# small_line.net
KiCad netlist of a schematic drawn in EAGLE
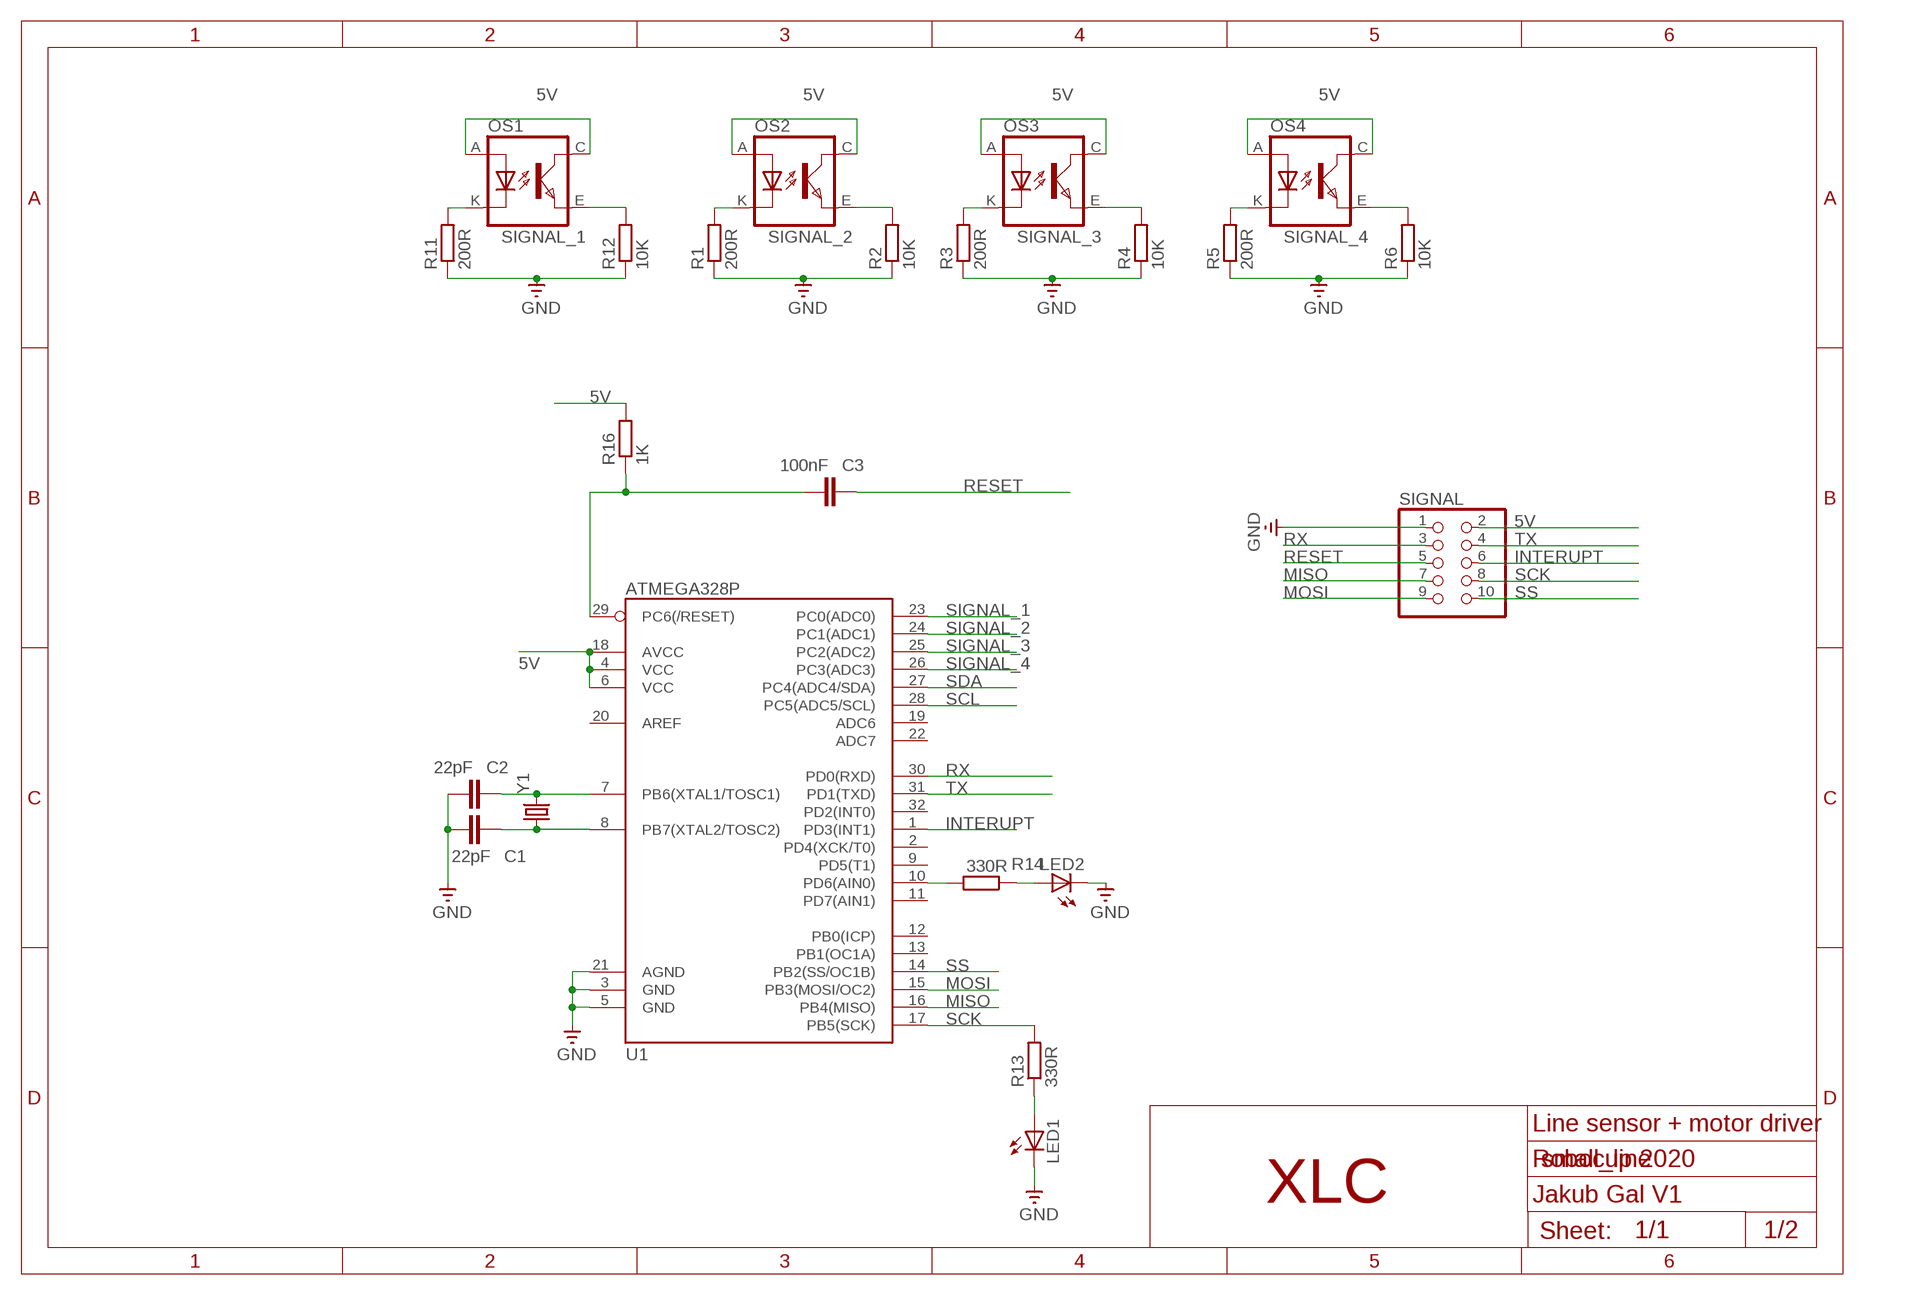
[diagram p0: schematic, sheet 1]

(export (version "E")
  (design (tool "Eeschema 10.0.6"))
  (components
    (comp (ref "C1")
      (value "22pF")
      (footprint "eagle-import:C0603")
      (libsource (lib "eagle-import") (part "C-EUC0603"))
    )
    (comp (ref "C2")
      (value "22pF")
      (footprint "eagle-import:C0603")
      (libsource (lib "eagle-import") (part "C-EUC0603"))
    )
    (comp (ref "C3")
      (value "100nF")
      (footprint "eagle-import:C0603")
      (libsource (lib "eagle-import") (part "C-EUC0603"))
    )
    (comp (ref "LED1")
      (value "LEDCHIPLED_0603")
      (footprint "eagle-import:CHIPLED_0603")
      (libsource (lib "eagle-import") (part "LEDCHIPLED_0603"))
    )
    (comp (ref "LED2")
      (value "LEDCHIPLED_0603")
      (footprint "eagle-import:CHIPLED_0603")
      (libsource (lib "eagle-import") (part "LEDCHIPLED_0603"))
    )
    (comp (ref "OS1")
      (value "TCRT5000")
      (footprint "eagle-import:TCRT5000")
      (libsource (lib "eagle-import") (part "TCRT5000"))
    )
    (comp (ref "OS2")
      (value "TCRT5000")
      (footprint "eagle-import:TCRT5000")
      (libsource (lib "eagle-import") (part "TCRT5000"))
    )
    (comp (ref "OS3")
      (value "TCRT5000")
      (footprint "eagle-import:TCRT5000")
      (libsource (lib "eagle-import") (part "TCRT5000"))
    )
    (comp (ref "OS4")
      (value "TCRT5000")
      (footprint "eagle-import:TCRT5000")
      (libsource (lib "eagle-import") (part "TCRT5000"))
    )
    (comp (ref "R1")
      (value "200R")
      (footprint "eagle-import:R0603")
      (libsource (lib "eagle-import") (part "R-EU_R0603"))
    )
    (comp (ref "R2")
      (value "10K")
      (footprint "eagle-import:R0603")
      (libsource (lib "eagle-import") (part "R-EU_R0603"))
    )
    (comp (ref "R3")
      (value "200R")
      (footprint "eagle-import:R0603")
      (libsource (lib "eagle-import") (part "R-EU_R0603"))
    )
    (comp (ref "R4")
      (value "10K")
      (footprint "eagle-import:R0603")
      (libsource (lib "eagle-import") (part "R-EU_R0603"))
    )
    (comp (ref "R5")
      (value "200R")
      (footprint "eagle-import:R0603")
      (libsource (lib "eagle-import") (part "R-EU_R0603"))
    )
    (comp (ref "R6")
      (value "10K")
      (footprint "eagle-import:R0603")
      (libsource (lib "eagle-import") (part "R-EU_R0603"))
    )
    (comp (ref "R11")
      (value "200R")
      (footprint "eagle-import:R0603")
      (libsource (lib "eagle-import") (part "R-EU_R0603"))
    )
    (comp (ref "R12")
      (value "10K")
      (footprint "eagle-import:R0603")
      (libsource (lib "eagle-import") (part "R-EU_R0603"))
    )
    (comp (ref "R13")
      (value "330R")
      (footprint "eagle-import:R0603")
      (libsource (lib "eagle-import") (part "R-EU_R0603"))
    )
    (comp (ref "R14")
      (value "330R")
      (footprint "eagle-import:R0603")
      (libsource (lib "eagle-import") (part "R-EU_R0603"))
    )
    (comp (ref "R16")
      (value "1K")
      (footprint "eagle-import:R0603")
      (libsource (lib "eagle-import") (part "R-EU_R0603"))
    )
    (comp (ref "SIGNAL")
      (value "PINHD-2X5")
      (footprint "eagle-import:2X05")
      (libsource (lib "eagle-import") (part "PINHD-2X5"))
    )
    (comp (ref "U1")
      (value "ATMEGA328P")
      (footprint "eagle-import:TQFP32-08")
      (libsource (lib "eagle-import") (part "ATMEGA328_SMT"))
    )
    (comp (ref "Y1")
      (value "CRYSTALHC49US")
      (footprint "eagle-import:HC49US")
      (libsource (lib "eagle-import") (part "CRYSTALHC49US"))
    )
  )
  (nets
    (net (code "1") (name "/5V") (class "Default")
      (node (ref "OS1") (pin "A") (pinfunction "ANODE_A") (pintype "passive"))
      (node (ref "OS1") (pin "C") (pinfunction "COLLECTOR_C") (pintype "passive"))
      (node (ref "OS2") (pin "A") (pinfunction "ANODE_A") (pintype "passive"))
      (node (ref "OS2") (pin "C") (pinfunction "COLLECTOR_C") (pintype "passive"))
      (node (ref "OS3") (pin "A") (pinfunction "ANODE_A") (pintype "passive"))
      (node (ref "OS3") (pin "C") (pinfunction "COLLECTOR_C") (pintype "passive"))
      (node (ref "OS4") (pin "A") (pinfunction "ANODE_A") (pintype "passive"))
      (node (ref "OS4") (pin "C") (pinfunction "COLLECTOR_C") (pintype "passive"))
      (node (ref "R16") (pin "2") (pinfunction "2_2") (pintype "passive"))
      (node (ref "SIGNAL") (pin "2") (pinfunction "2_2") (pintype "passive"))
      (node (ref "U1") (pin "18") (pinfunction "AVCC_18") (pintype "bidirectional"))
      (node (ref "U1") (pin "4") (pinfunction "VCC_4") (pintype "bidirectional"))
      (node (ref "U1") (pin "6") (pinfunction "VCC_6") (pintype "bidirectional"))
    )
    (net (code "2") (name "/INTERUPT") (class "Default")
      (node (ref "SIGNAL") (pin "6") (pinfunction "6_6") (pintype "passive"))
      (node (ref "U1") (pin "1") (pinfunction "PD3(INT1)_1") (pintype "bidirectional"))
    )
    (net (code "3") (name "/MISO") (class "Default")
      (node (ref "SIGNAL") (pin "7") (pinfunction "7_7") (pintype "passive"))
      (node (ref "U1") (pin "16") (pinfunction "PB4(MISO)_16") (pintype "bidirectional"))
    )
    (net (code "4") (name "/MOSI") (class "Default")
      (node (ref "SIGNAL") (pin "9") (pinfunction "9_9") (pintype "passive"))
      (node (ref "U1") (pin "15") (pinfunction "PB3(MOSI/OC2)_15") (pintype "bidirectional"))
    )
    (net (code "5") (name "/RESET") (class "Default")
      (node (ref "C3") (pin "2") (pinfunction "2_2") (pintype "passive"))
      (node (ref "SIGNAL") (pin "5") (pinfunction "5_5") (pintype "passive"))
    )
    (net (code "6") (name "/RX") (class "Default")
      (node (ref "SIGNAL") (pin "3") (pinfunction "3_3") (pintype "passive"))
      (node (ref "U1") (pin "30") (pinfunction "PD0(RXD)_30") (pintype "bidirectional"))
    )
    (net (code "7") (name "/SCK") (class "Default")
      (node (ref "R13") (pin "2") (pinfunction "2_2") (pintype "passive"))
      (node (ref "SIGNAL") (pin "8") (pinfunction "8_8") (pintype "passive"))
      (node (ref "U1") (pin "17") (pinfunction "PB5(SCK)_17") (pintype "bidirectional"))
    )
    (net (code "8") (name "/SCL") (class "Default")
      (node (ref "U1") (pin "28") (pinfunction "PC5(ADC5/SCL)_28") (pintype "bidirectional"))
    )
    (net (code "9") (name "/SDA") (class "Default")
      (node (ref "U1") (pin "27") (pinfunction "PC4(ADC4/SDA)_27") (pintype "bidirectional"))
    )
    (net (code "10") (name "/SIGNAL_1") (class "Default")
      (node (ref "OS1") (pin "E") (pinfunction "EMITTER_E") (pintype "passive"))
      (node (ref "R12") (pin "2") (pinfunction "2_2") (pintype "passive"))
      (node (ref "U1") (pin "23") (pinfunction "PC0(ADC0)_23") (pintype "bidirectional"))
    )
    (net (code "11") (name "/SIGNAL_2") (class "Default")
      (node (ref "OS2") (pin "E") (pinfunction "EMITTER_E") (pintype "passive"))
      (node (ref "R2") (pin "2") (pinfunction "2_2") (pintype "passive"))
      (node (ref "U1") (pin "24") (pinfunction "PC1(ADC1)_24") (pintype "bidirectional"))
    )
    (net (code "12") (name "/SIGNAL_3") (class "Default")
      (node (ref "OS3") (pin "E") (pinfunction "EMITTER_E") (pintype "passive"))
      (node (ref "R4") (pin "2") (pinfunction "2_2") (pintype "passive"))
      (node (ref "U1") (pin "25") (pinfunction "PC2(ADC2)_25") (pintype "bidirectional"))
    )
    (net (code "13") (name "/SIGNAL_4") (class "Default")
      (node (ref "OS4") (pin "E") (pinfunction "EMITTER_E") (pintype "passive"))
      (node (ref "R6") (pin "2") (pinfunction "2_2") (pintype "passive"))
      (node (ref "U1") (pin "26") (pinfunction "PC3(ADC3)_26") (pintype "bidirectional"))
    )
    (net (code "14") (name "/SS") (class "Default")
      (node (ref "SIGNAL") (pin "10") (pinfunction "10_10") (pintype "passive"))
      (node (ref "U1") (pin "14") (pinfunction "PB2(SS/OC1B)_14") (pintype "bidirectional"))
    )
    (net (code "15") (name "/TX") (class "Default")
      (node (ref "SIGNAL") (pin "4") (pinfunction "4_4") (pintype "passive"))
      (node (ref "U1") (pin "31") (pinfunction "PD1(TXD)_31") (pintype "bidirectional"))
    )
    (net (code "16") (name "GND") (class "Default")
      (node (ref "C1") (pin "1") (pinfunction "1_1") (pintype "passive"))
      (node (ref "C2") (pin "1") (pinfunction "1_1") (pintype "passive"))
      (node (ref "LED1") (pin "C") (pinfunction "C_C") (pintype "passive"))
      (node (ref "LED2") (pin "C") (pinfunction "C_C") (pintype "passive"))
      (node (ref "R1") (pin "1") (pinfunction "1_1") (pintype "passive"))
      (node (ref "R11") (pin "1") (pinfunction "1_1") (pintype "passive"))
      (node (ref "R12") (pin "1") (pinfunction "1_1") (pintype "passive"))
      (node (ref "R2") (pin "1") (pinfunction "1_1") (pintype "passive"))
      (node (ref "R3") (pin "1") (pinfunction "1_1") (pintype "passive"))
      (node (ref "R4") (pin "1") (pinfunction "1_1") (pintype "passive"))
      (node (ref "R5") (pin "1") (pinfunction "1_1") (pintype "passive"))
      (node (ref "R6") (pin "1") (pinfunction "1_1") (pintype "passive"))
      (node (ref "SIGNAL") (pin "1") (pinfunction "1_1") (pintype "passive"))
      (node (ref "U1") (pin "21") (pinfunction "AGND_21") (pintype "bidirectional"))
      (node (ref "U1") (pin "3") (pinfunction "GND_3") (pintype "bidirectional"))
      (node (ref "U1") (pin "5") (pinfunction "GND_5") (pintype "bidirectional"))
    )
    (net (code "17") (name "Net-(LED1-PadA)") (class "Default")
      (node (ref "LED1") (pin "A") (pinfunction "A_A") (pintype "passive"))
      (node (ref "R13") (pin "1") (pinfunction "1_1") (pintype "passive"))
    )
    (net (code "18") (name "Net-(LED2-PadA)") (class "Default")
      (node (ref "LED2") (pin "A") (pinfunction "A_A") (pintype "passive"))
      (node (ref "R14") (pin "1") (pinfunction "1_1") (pintype "passive"))
    )
    (net (code "19") (name "Net-(OS1-CATHODE)") (class "Default")
      (node (ref "OS1") (pin "K") (pinfunction "CATHODE_K") (pintype "passive"))
      (node (ref "R11") (pin "2") (pinfunction "2_2") (pintype "passive"))
    )
    (net (code "20") (name "Net-(OS2-CATHODE)") (class "Default")
      (node (ref "OS2") (pin "K") (pinfunction "CATHODE_K") (pintype "passive"))
      (node (ref "R1") (pin "2") (pinfunction "2_2") (pintype "passive"))
    )
    (net (code "21") (name "Net-(OS3-CATHODE)") (class "Default")
      (node (ref "OS3") (pin "K") (pinfunction "CATHODE_K") (pintype "passive"))
      (node (ref "R3") (pin "2") (pinfunction "2_2") (pintype "passive"))
    )
    (net (code "22") (name "Net-(OS4-CATHODE)") (class "Default")
      (node (ref "OS4") (pin "K") (pinfunction "CATHODE_K") (pintype "passive"))
      (node (ref "R5") (pin "2") (pinfunction "2_2") (pintype "passive"))
    )
    (net (code "23") (name "Net-(U1-PB6(XTAL1{slash}TOSC1))") (class "Default")
      (node (ref "C2") (pin "2") (pinfunction "2_2") (pintype "passive"))
      (node (ref "U1") (pin "7") (pinfunction "PB6(XTAL1/TOSC1)_7") (pintype "bidirectional"))
      (node (ref "Y1") (pin "2") (pinfunction "2_2") (pintype "passive"))
    )
    (net (code "24") (name "Net-(U1-PB7(XTAL2{slash}TOSC2))") (class "Default")
      (node (ref "C1") (pin "2") (pinfunction "2_2") (pintype "passive"))
      (node (ref "U1") (pin "8") (pinfunction "PB7(XTAL2/TOSC2)_8") (pintype "bidirectional"))
      (node (ref "Y1") (pin "1") (pinfunction "1_1") (pintype "passive"))
    )
    (net (code "25") (name "Net-(U1-PC6({slash}RESET))") (class "Default")
      (node (ref "C3") (pin "1") (pinfunction "1_1") (pintype "passive"))
      (node (ref "R16") (pin "1") (pinfunction "1_1") (pintype "passive"))
      (node (ref "U1") (pin "29") (pinfunction "PC6(/RESET)_29") (pintype "bidirectional"))
    )
    (net (code "26") (name "Net-(U1-PD6(AIN0))") (class "Default")
      (node (ref "R14") (pin "2") (pinfunction "2_2") (pintype "passive"))
      (node (ref "U1") (pin "10") (pinfunction "PD6(AIN0)_10") (pintype "bidirectional"))
    )
    (net (code "27") (name "unconnected-(U1-ADC6-Pad19)") (class "Default")
      (node (ref "U1") (pin "19") (pinfunction "ADC6_19") (pintype "bidirectional"))
    )
    (net (code "28") (name "unconnected-(U1-ADC7-Pad22)") (class "Default")
      (node (ref "U1") (pin "22") (pinfunction "ADC7_22") (pintype "bidirectional"))
    )
    (net (code "29") (name "unconnected-(U1-AREF-Pad20)") (class "Default")
      (node (ref "U1") (pin "20") (pinfunction "AREF_20") (pintype "bidirectional"))
    )
    (net (code "30") (name "unconnected-(U1-PB0(ICP)-Pad12)") (class "Default")
      (node (ref "U1") (pin "12") (pinfunction "PB0(ICP)_12") (pintype "bidirectional"))
    )
    (net (code "31") (name "unconnected-(U1-PB1(OC1A)-Pad13)") (class "Default")
      (node (ref "U1") (pin "13") (pinfunction "PB1(OC1A)_13") (pintype "bidirectional"))
    )
    (net (code "32") (name "unconnected-(U1-PD2(INT0)-Pad32)") (class "Default")
      (node (ref "U1") (pin "32") (pinfunction "PD2(INT0)_32") (pintype "bidirectional"))
    )
    (net (code "33") (name "unconnected-(U1-PD4(XCK{slash}T0)-Pad2)") (class "Default")
      (node (ref "U1") (pin "2") (pinfunction "PD4(XCK/T0)_2") (pintype "bidirectional"))
    )
    (net (code "34") (name "unconnected-(U1-PD5(T1)-Pad9)") (class "Default")
      (node (ref "U1") (pin "9") (pinfunction "PD5(T1)_9") (pintype "bidirectional"))
    )
    (net (code "35") (name "unconnected-(U1-PD7(AIN1)-Pad11)") (class "Default")
      (node (ref "U1") (pin "11") (pinfunction "PD7(AIN1)_11") (pintype "bidirectional"))
    )
  )
)
